# monitor.net
KiCad netlist of a schematic drawn in Altium Designer
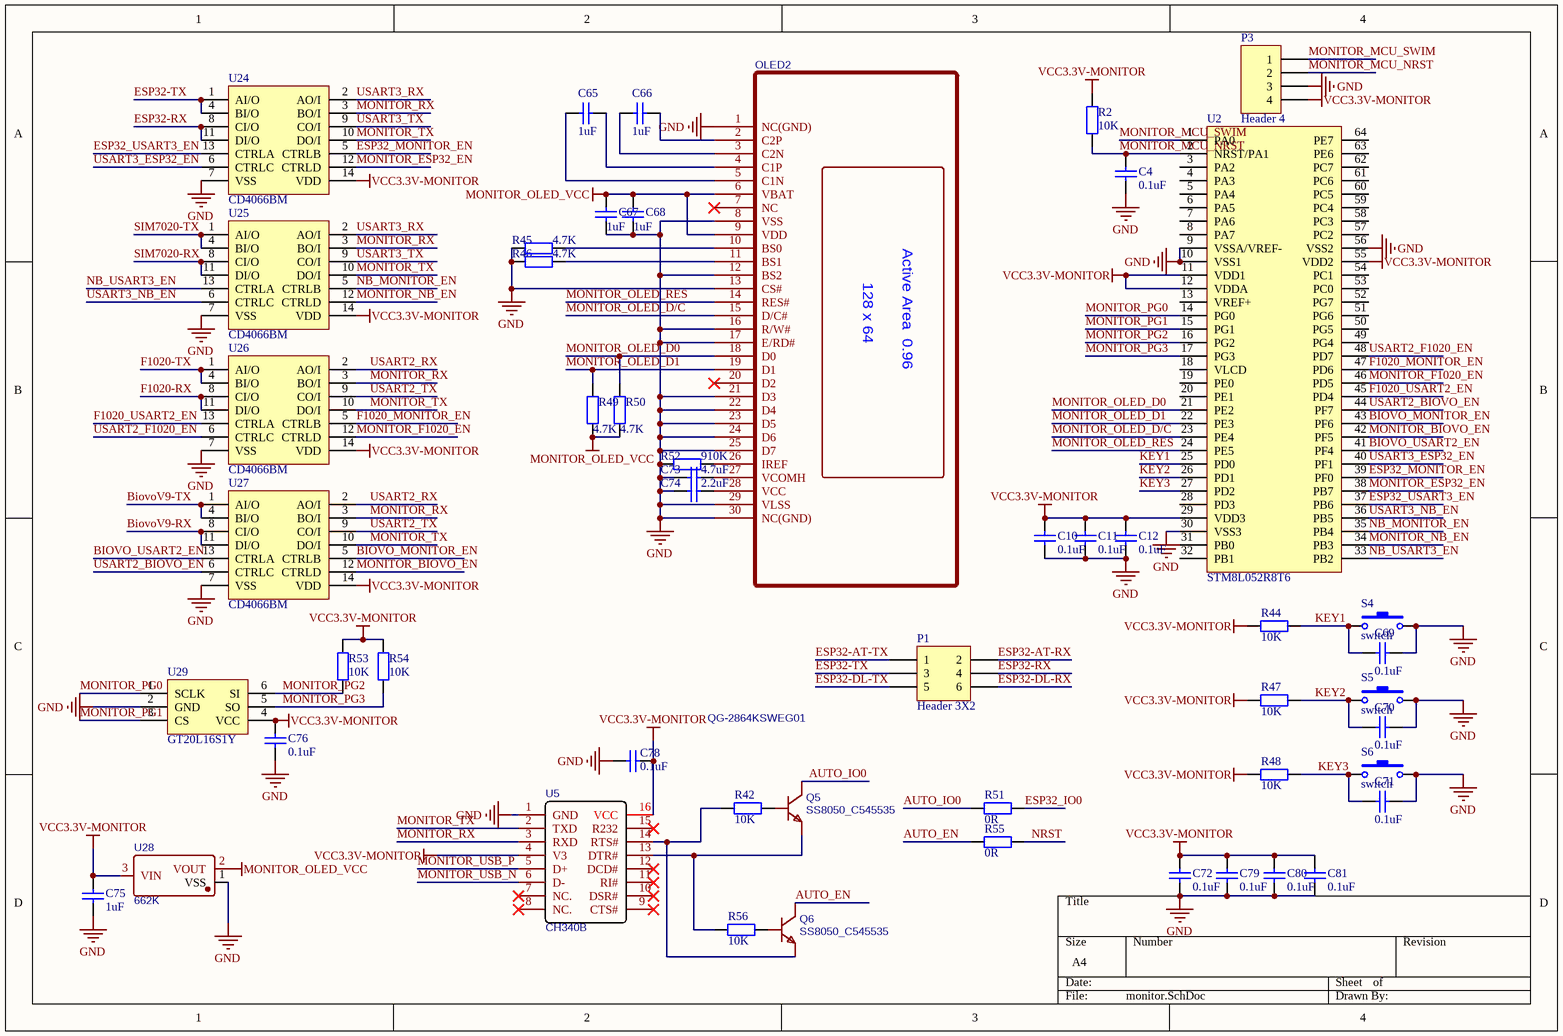
[diagram p0: monitor.SchDoc]

(export (version "E")
  (design (tool "Eeschema 10.0.6"))
  (components
    (comp (ref "C4")
      (value "0.1uF")
      (footprint "0603_C")
      (description "贴片电容，0603")
      (libsource (lib "stm8l052r8t6开发板") (part "Cap"))
    )
    (comp (ref "C10")
      (value "0.1uF")
      (footprint "0603_C")
      (description "贴片电容，0603")
      (libsource (lib "stm8l052r8t6开发板") (part "Cap"))
    )
    (comp (ref "C11")
      (value "0.1uF")
      (footprint "0603_C")
      (description "贴片电容，0603")
      (libsource (lib "stm8l052r8t6开发板") (part "Cap"))
    )
    (comp (ref "C12")
      (value "0.1uF")
      (footprint "0603_C")
      (description "贴片电容，0603")
      (libsource (lib "stm8l052r8t6开发板") (part "Cap"))
    )
    (comp (ref "C65")
      (value "1uF")
      (footprint "0603_C")
      (description "贴片电容，0603")
      (libsource (lib "stm8l052r8t6开发板") (part "Cap"))
    )
    (comp (ref "C66")
      (value "1uF")
      (footprint "0603_C")
      (description "贴片电容，0603")
      (libsource (lib "stm8l052r8t6开发板") (part "Cap"))
    )
    (comp (ref "C67")
      (value "1uF")
      (footprint "0603_C")
      (description "贴片电容，0603")
      (libsource (lib "stm8l052r8t6开发板") (part "Cap"))
    )
    (comp (ref "C68")
      (value "1uF")
      (footprint "0603_C")
      (description "贴片电容，0603")
      (libsource (lib "stm8l052r8t6开发板") (part "Cap"))
    )
    (comp (ref "C69")
      (value "0.1uF")
      (footprint "0603_C")
      (description "贴片电容，0603")
      (libsource (lib "extendBoard") (part "Cap"))
    )
    (comp (ref "C70")
      (value "0.1uF")
      (footprint "0603_C")
      (description "贴片电容，0603")
      (libsource (lib "extendBoard") (part "Cap"))
    )
    (comp (ref "C71")
      (value "0.1uF")
      (footprint "0603_C")
      (description "贴片电容，0603")
      (libsource (lib "extendBoard") (part "Cap"))
    )
    (comp (ref "C72")
      (value "0.1uF")
      (footprint "0603_C")
      (description "贴片电容，0603")
      (libsource (lib "extendBoard") (part "Cap"))
    )
    (comp (ref "C73")
      (value "4.7uF")
      (footprint "0603_C")
      (description "贴片电容，0603")
      (libsource (lib "stm8l052r8t6开发板") (part "Cap"))
    )
    (comp (ref "C74")
      (value "2.2uF")
      (footprint "0603_C")
      (description "贴片电容，0603")
      (libsource (lib "stm8l052r8t6开发板") (part "Cap"))
    )
    (comp (ref "C75")
      (value "1uF")
      (footprint "0603_C")
      (description "贴片电容，0603")
      (libsource (lib "stm8l052r8t6开发板") (part "Cap"))
    )
    (comp (ref "C76")
      (value "0.1uF")
      (footprint "0603_C")
      (description "贴片电容，0603")
      (libsource (lib "stm8l052r8t6开发板") (part "Cap"))
    )
    (comp (ref "C78")
      (value "0.1uF")
      (footprint "0603_C")
      (description "贴片电容，0603")
      (libsource (lib "extendBoard") (part "Cap"))
    )
    (comp (ref "C79")
      (value "0.1uF")
      (footprint "0603_C")
      (description "贴片电容，0603")
      (libsource (lib "extendBoard") (part "Cap"))
    )
    (comp (ref "C80")
      (value "0.1uF")
      (footprint "0603_C")
      (description "贴片电容，0603")
      (libsource (lib "extendBoard") (part "Cap"))
    )
    (comp (ref "C81")
      (value "0.1uF")
      (footprint "0603_C")
      (description "贴片电容，0603")
      (libsource (lib "extendBoard") (part "Cap"))
    )
    (comp (ref "OLED2")
      (value "QG-2864KSWEG01")
      (footprint "OLED-SMD_QG-2864KSWEG01-flod")
      (description "128x64 单色白色，QG-2864KSWEG01")
      (fields (field (name "BOM_SUPPLIER PART") "C85007"))
      (libsource (lib "stm8l052r8t6开发板") (part "QG-2864KSWEG01"))
    )
    (comp (ref "P1")
      (value "Header 3X2")
      (footprint "HDR2X3")
      (description "Header, 3-Pin, Dual row")
      (fields (field (name "PUBLISHER") "Altium Limited"))
      (libsource (lib "Miscellaneous Connectors") (part "Header 3X2"))
    )
    (comp (ref "P3")
      (value "Header 4")
      (footprint "HDR1X4")
      (description "不焊")
      (fields (field (name "PUBLISHER") "Altium Limited"))
      (libsource (lib "Miscellaneous Connectors") (part "Header 4"))
    )
    (comp (ref "Q5")
      (value "SS8050_C545535")
      (footprint "SOT-23-3_L2.9-W1.3-P1.90-LS2.4-BR")
      (description "S8050,SOT-23")
      (libsource (lib "stm8l052r8t6开发板") (part "SS8050_C545535"))
    )
    (comp (ref "Q6")
      (value "SS8050_C545535")
      (footprint "SOT-23-3_L2.9-W1.3-P1.90-LS2.4-BR")
      (description "S8050,SOT-23")
      (libsource (lib "stm8l052r8t6开发板") (part "SS8050_C545535"))
    )
    (comp (ref "R2")
      (value "10K")
      (footprint "0603_R")
      (description "贴片电阻，0603")
      (libsource (lib "stm8l052r8t6开发板") (part "Res2"))
    )
    (comp (ref "R42")
      (value "10K")
      (footprint "0603_R")
      (description "贴片电阻，0603")
      (libsource (lib "extendBoard") (part "Res2"))
    )
    (comp (ref "R44")
      (value "10K")
      (footprint "0603_R")
      (description "贴片电阻，0603")
      (libsource (lib "") (part "Res2_2"))
    )
    (comp (ref "R45")
      (value "4.7K")
      (footprint "0603_R")
      (description "贴片电阻，0603")
      (libsource (lib "") (part "Res2_1"))
    )
    (comp (ref "R46")
      (value "4.7K")
      (footprint "0603_R")
      (description "贴片电阻，0603")
      (libsource (lib "") (part "Res2_1"))
    )
    (comp (ref "R47")
      (value "10K")
      (footprint "0603_R")
      (description "贴片电阻，0603")
      (libsource (lib "") (part "Res2_2"))
    )
    (comp (ref "R48")
      (value "10K")
      (footprint "0603_R")
      (description "贴片电阻，0603")
      (libsource (lib "") (part "Res2_2"))
    )
    (comp (ref "R49")
      (value "4.7K")
      (footprint "0603_R")
      (description "贴片电阻，0603")
      (libsource (lib "stm8l052r8t6开发板") (part "Res2"))
    )
    (comp (ref "R50")
      (value "4.7K")
      (footprint "0603_R")
      (description "贴片电阻，0603")
      (libsource (lib "stm8l052r8t6开发板") (part "Res2"))
    )
    (comp (ref "R51")
      (value "0R")
      (footprint "0603_R")
      (description "贴片电阻，0603")
      (libsource (lib "extendBoard") (part "Res2"))
    )
    (comp (ref "R52")
      (value "910K")
      (footprint "0603_R")
      (description "贴片电阻，0603")
      (libsource (lib "") (part "Res2_2"))
    )
    (comp (ref "R53")
      (value "10K")
      (footprint "0603_R")
      (description "贴片电阻，0603")
      (libsource (lib "stm8l052r8t6开发板") (part "Res2"))
    )
    (comp (ref "R54")
      (value "10K")
      (footprint "0603_R")
      (description "贴片电阻，0603")
      (libsource (lib "stm8l052r8t6开发板") (part "Res2"))
    )
    (comp (ref "R55")
      (value "0R")
      (footprint "0603_R")
      (description "贴片电阻，0603")
      (libsource (lib "extendBoard") (part "Res2"))
    )
    (comp (ref "R56")
      (value "10K")
      (footprint "0603_R")
      (description "贴片电阻，0603")
      (libsource (lib "extendBoard") (part "Res2"))
    )
    (comp (ref "S4")
      (value "switch")
      (footprint "SW-SMD_4P-L6.2-W6.2-P4.50-LS9.0")
      (description "贴片按键，6*6*5")
      (libsource (lib "stm8l052r8t6开发板") (part "switch"))
    )
    (comp (ref "S5")
      (value "switch")
      (footprint "SW-SMD_4P-L6.2-W6.2-P4.50-LS9.0")
      (description "贴片按键，6*6*5")
      (libsource (lib "stm8l052r8t6开发板") (part "switch"))
    )
    (comp (ref "S6")
      (value "switch")
      (footprint "SW-SMD_4P-L6.2-W6.2-P4.50-LS9.0")
      (description "贴片按键，6*6*5")
      (libsource (lib "stm8l052r8t6开发板") (part "switch"))
    )
    (comp (ref "U2")
      (value "STM8L052R8T6")
      (footprint "LQFP-64_10X10X05P")
      (description "STM8L052R8T6,LQFP-64_10x10x05P")
      (libsource (lib "stm8l052r8t6开发板") (part "STM8L052R8T6"))
    )
    (comp (ref "U5")
      (value "CH340B")
      (footprint "SOP-16_L10.0-W3.9-P1.27-LS6.0-BL")
      (description "CH340B,SOP-16_150mil")
      (libsource (lib "stm8l052r8t6开发板") (part "CH340C"))
    )
    (comp (ref "U24")
      (value "CD4066BM")
      (footprint "SOIC-14_L8.7-W3.9-P1.27-LS6.0-BL")
      (description "双向 FET 开关,CD4066BM,SOIC-14")
      (libsource (lib "stm8l052r8t6开发板") (part "CD4066B"))
    )
    (comp (ref "U25")
      (value "CD4066BM")
      (footprint "SOIC-14_L8.7-W3.9-P1.27-LS6.0-BL")
      (description "双向 FET 开关,CD4066BM,SOIC-14")
      (libsource (lib "stm8l052r8t6开发板") (part "CD4066B"))
    )
    (comp (ref "U26")
      (value "CD4066BM")
      (footprint "SOIC-14_L8.7-W3.9-P1.27-LS6.0-BL")
      (description "双向 FET 开关,CD4066BM,SOIC-14")
      (libsource (lib "stm8l052r8t6开发板") (part "CD4066B"))
    )
    (comp (ref "U27")
      (value "CD4066BM")
      (footprint "SOIC-14_L8.7-W3.9-P1.27-LS6.0-BL")
      (description "双向 FET 开关,CD4066BM,SOIC-14")
      (libsource (lib "stm8l052r8t6开发板") (part "CD4066B"))
    )
    (comp (ref "U28")
      (value "662K")
      (footprint "SOT-23(SOT-23-3)")
      (description "线性稳压器662k,SOT23-3")
      (libsource (lib "stm8l052r8t6开发板") (part "662K"))
    )
    (comp (ref "U29")
      (value "GT20L16S1Y")
      (footprint "SOT-23-6")
      (description "字库芯片， SOT-23-6")
      (libsource (lib "stm8l052r8t6开发板") (part "GT20L16S1Y"))
    )
  )
  (nets
    (net (code "1") (name "/AUTO_EN") (class "Default")
      (node (ref "Q6") (pin "3") (pinfunction "C_3") (pintype "passive"))
      (node (ref "R55") (pin "2") (pinfunction "2_2") (pintype "passive"))
    )
    (net (code "2") (name "/AUTO_IO0") (class "Default")
      (node (ref "Q5") (pin "3") (pinfunction "C_3") (pintype "passive"))
      (node (ref "R51") (pin "2") (pinfunction "2_2") (pintype "passive"))
    )
    (net (code "3") (name "/BIOVO_MONITOR_EN") (class "Default")
      (node (ref "U2") (pin "43") (pinfunction "PF6_43") (pintype "passive"))
      (node (ref "U27") (pin "5") (pinfunction "CTRLB_5") (pintype "passive"))
    )
    (net (code "4") (name "/BIOVO_USART2_EN") (class "Default")
      (node (ref "U2") (pin "41") (pinfunction "PF4_41") (pintype "passive"))
      (node (ref "U27") (pin "13") (pinfunction "CTRLA_13") (pintype "passive"))
    )
    (net (code "5") (name "/BiovoV9-RX") (class "Default")
      (node (ref "U27") (pin "11") (pinfunction "DI/O_11") (pintype "passive"))
      (node (ref "U27") (pin "8") (pinfunction "CI/O_8") (pintype "passive"))
    )
    (net (code "6") (name "/BiovoV9-TX") (class "Default")
      (node (ref "U27") (pin "1") (pinfunction "AI/O_1") (pintype "passive"))
      (node (ref "U27") (pin "4") (pinfunction "BI/O_4") (pintype "passive"))
    )
    (net (code "7") (name "/ESP32-AT-RX") (class "Default")
      (node (ref "P1") (pin "2") (pinfunction "2_2") (pintype "passive"))
    )
    (net (code "8") (name "/ESP32-AT-TX") (class "Default")
      (node (ref "P1") (pin "1") (pinfunction "1_1") (pintype "passive"))
    )
    (net (code "9") (name "/ESP32-DL-RX") (class "Default")
      (node (ref "P1") (pin "6") (pinfunction "6_6") (pintype "passive"))
    )
    (net (code "10") (name "/ESP32-DL-TX") (class "Default")
      (node (ref "P1") (pin "5") (pinfunction "5_5") (pintype "passive"))
    )
    (net (code "11") (name "/ESP32-RX") (class "Default")
      (node (ref "P1") (pin "4") (pinfunction "4_4") (pintype "passive"))
      (node (ref "U24") (pin "11") (pinfunction "DI/O_11") (pintype "passive"))
      (node (ref "U24") (pin "8") (pinfunction "CI/O_8") (pintype "passive"))
    )
    (net (code "12") (name "/ESP32-TX") (class "Default")
      (node (ref "P1") (pin "3") (pinfunction "3_3") (pintype "passive"))
      (node (ref "U24") (pin "1") (pinfunction "AI/O_1") (pintype "passive"))
      (node (ref "U24") (pin "4") (pinfunction "BI/O_4") (pintype "passive"))
    )
    (net (code "13") (name "/ESP32_IO0") (class "Default")
      (node (ref "R51") (pin "1") (pinfunction "1_1") (pintype "passive"))
    )
    (net (code "14") (name "/ESP32_MONITOR_EN") (class "Default")
      (node (ref "U2") (pin "39") (pinfunction "PF0_39") (pintype "passive"))
      (node (ref "U24") (pin "5") (pinfunction "CTRLB_5") (pintype "passive"))
    )
    (net (code "15") (name "/ESP32_USART3_EN") (class "Default")
      (node (ref "U2") (pin "37") (pinfunction "PB6_37") (pintype "passive"))
      (node (ref "U24") (pin "13") (pinfunction "CTRLA_13") (pintype "passive"))
    )
    (net (code "16") (name "/F1020-RX") (class "Default")
      (node (ref "U26") (pin "11") (pinfunction "DI/O_11") (pintype "passive"))
      (node (ref "U26") (pin "8") (pinfunction "CI/O_8") (pintype "passive"))
    )
    (net (code "17") (name "/F1020-TX") (class "Default")
      (node (ref "U26") (pin "1") (pinfunction "AI/O_1") (pintype "passive"))
      (node (ref "U26") (pin "4") (pinfunction "BI/O_4") (pintype "passive"))
    )
    (net (code "18") (name "/F1020_MONITOR_EN") (class "Default")
      (node (ref "U2") (pin "47") (pinfunction "PD6_47") (pintype "passive"))
      (node (ref "U26") (pin "5") (pinfunction "CTRLB_5") (pintype "passive"))
    )
    (net (code "19") (name "/F1020_USART2_EN") (class "Default")
      (node (ref "U2") (pin "45") (pinfunction "PD4_45") (pintype "passive"))
      (node (ref "U26") (pin "13") (pinfunction "CTRLA_13") (pintype "passive"))
    )
    (net (code "20") (name "/KEY1") (class "Default")
      (node (ref "C69") (pin "2") (pinfunction "2_2") (pintype "passive"))
      (node (ref "R44") (pin "1") (pinfunction "1_1") (pintype "passive"))
      (node (ref "S4") (pin "1") (pinfunction "1_1") (pintype "passive"))
      (node (ref "U2") (pin "25") (pinfunction "PD0_25") (pintype "passive"))
    )
    (net (code "21") (name "/KEY2") (class "Default")
      (node (ref "C70") (pin "2") (pinfunction "2_2") (pintype "passive"))
      (node (ref "R47") (pin "1") (pinfunction "1_1") (pintype "passive"))
      (node (ref "S5") (pin "1") (pinfunction "1_1") (pintype "passive"))
      (node (ref "U2") (pin "26") (pinfunction "PD1_26") (pintype "passive"))
    )
    (net (code "22") (name "/KEY3") (class "Default")
      (node (ref "C71") (pin "2") (pinfunction "2_2") (pintype "passive"))
      (node (ref "R48") (pin "1") (pinfunction "1_1") (pintype "passive"))
      (node (ref "S6") (pin "1") (pinfunction "1_1") (pintype "passive"))
      (node (ref "U2") (pin "27") (pinfunction "PD2_27") (pintype "passive"))
    )
    (net (code "23") (name "/MONITOR_BIOVO_EN") (class "Default")
      (node (ref "U2") (pin "42") (pinfunction "PF5_42") (pintype "passive"))
      (node (ref "U27") (pin "12") (pinfunction "CTRLD_12") (pintype "passive"))
    )
    (net (code "24") (name "/MONITOR_ESP32_EN") (class "Default")
      (node (ref "U2") (pin "38") (pinfunction "PB7_38") (pintype "passive"))
      (node (ref "U24") (pin "12") (pinfunction "CTRLD_12") (pintype "passive"))
    )
    (net (code "25") (name "/MONITOR_F1020_EN") (class "Default")
      (node (ref "U2") (pin "46") (pinfunction "PD5_46") (pintype "passive"))
      (node (ref "U26") (pin "12") (pinfunction "CTRLD_12") (pintype "passive"))
    )
    (net (code "26") (name "/MONITOR_MCU_NRST") (class "Default")
      (node (ref "C4") (pin "2") (pinfunction "2_2") (pintype "passive"))
      (node (ref "P3") (pin "2") (pinfunction "2_2") (pintype "passive"))
      (node (ref "R2") (pin "1") (pinfunction "1_1") (pintype "passive"))
      (node (ref "U2") (pin "2") (pinfunction "NRST/PA1_2") (pintype "passive"))
    )
    (net (code "27") (name "/MONITOR_MCU_SWIM") (class "Default")
      (node (ref "P3") (pin "1") (pinfunction "1_1") (pintype "passive"))
      (node (ref "U2") (pin "1") (pinfunction "PA0_1") (pintype "passive"))
    )
    (net (code "28") (name "/MONITOR_NB_EN") (class "Default")
      (node (ref "U2") (pin "34") (pinfunction "PB3_34") (pintype "passive"))
      (node (ref "U25") (pin "12") (pinfunction "CTRLD_12") (pintype "passive"))
    )
    (net (code "29") (name "/MONITOR_OLED_D0") (class "Default")
      (node (ref "OLED2") (pin "18") (pinfunction "D0_18") (pintype "passive"))
      (node (ref "R50") (pin "2") (pinfunction "2_2") (pintype "passive"))
      (node (ref "U2") (pin "21") (pinfunction "PE2_21") (pintype "passive"))
    )
    (net (code "30") (name "/MONITOR_OLED_D1") (class "Default")
      (node (ref "OLED2") (pin "19") (pinfunction "D1_19") (pintype "passive"))
      (node (ref "R49") (pin "2") (pinfunction "2_2") (pintype "passive"))
      (node (ref "U2") (pin "22") (pinfunction "PE3_22") (pintype "passive"))
    )
    (net (code "31") (name "/MONITOR_OLED_D{slash}C") (class "Default")
      (node (ref "OLED2") (pin "15") (pinfunction "D/C#_15") (pintype "passive"))
      (node (ref "U2") (pin "23") (pinfunction "PE4_23") (pintype "passive"))
    )
    (net (code "32") (name "/MONITOR_OLED_RES") (class "Default")
      (node (ref "OLED2") (pin "14") (pinfunction "RES#_14") (pintype "passive"))
      (node (ref "U2") (pin "24") (pinfunction "PE5_24") (pintype "passive"))
    )
    (net (code "33") (name "/MONITOR_PG0") (class "Default")
      (node (ref "U2") (pin "14") (pinfunction "PG0_14") (pintype "passive"))
      (node (ref "U29") (pin "1") (pinfunction "SCLK_1") (pintype "passive"))
    )
    (net (code "34") (name "/MONITOR_PG1") (class "Default")
      (node (ref "U2") (pin "15") (pinfunction "PG1_15") (pintype "passive"))
      (node (ref "U29") (pin "3") (pinfunction "CS_3") (pintype "passive"))
    )
    (net (code "35") (name "/MONITOR_PG2") (class "Default")
      (node (ref "R53") (pin "1") (pinfunction "1_1") (pintype "passive"))
      (node (ref "U2") (pin "16") (pinfunction "PG2_16") (pintype "passive"))
      (node (ref "U29") (pin "6") (pinfunction "SI_6") (pintype "passive"))
    )
    (net (code "36") (name "/MONITOR_PG3") (class "Default")
      (node (ref "R54") (pin "1") (pinfunction "1_1") (pintype "passive"))
      (node (ref "U2") (pin "17") (pinfunction "PG3_17") (pintype "passive"))
      (node (ref "U29") (pin "5") (pinfunction "SO_5") (pintype "passive"))
    )
    (net (code "37") (name "/MONITOR_RX") (class "Default")
      (node (ref "U24") (pin "3") (pinfunction "BO/I_3") (pintype "passive"))
      (node (ref "U25") (pin "3") (pinfunction "BO/I_3") (pintype "passive"))
      (node (ref "U26") (pin "3") (pinfunction "BO/I_3") (pintype "passive"))
      (node (ref "U27") (pin "3") (pinfunction "BO/I_3") (pintype "passive"))
      (node (ref "U5") (pin "3") (pinfunction "RXD_3") (pintype "passive"))
    )
    (net (code "38") (name "/MONITOR_TX") (class "Default")
      (node (ref "U24") (pin "10") (pinfunction "DO/I_10") (pintype "passive"))
      (node (ref "U25") (pin "10") (pinfunction "DO/I_10") (pintype "passive"))
      (node (ref "U26") (pin "10") (pinfunction "DO/I_10") (pintype "passive"))
      (node (ref "U27") (pin "10") (pinfunction "DO/I_10") (pintype "passive"))
      (node (ref "U5") (pin "2") (pinfunction "TXD_2") (pintype "passive"))
    )
    (net (code "39") (name "/MONITOR_USB_N") (class "Default")
      (node (ref "U5") (pin "6") (pinfunction "D-_6") (pintype "passive"))
    )
    (net (code "40") (name "/MONITOR_USB_P") (class "Default")
      (node (ref "U5") (pin "5") (pinfunction "D+_5") (pintype "passive"))
    )
    (net (code "41") (name "/NB_MONITOR_EN") (class "Default")
      (node (ref "U2") (pin "35") (pinfunction "PB4_35") (pintype "passive"))
      (node (ref "U25") (pin "5") (pinfunction "CTRLB_5") (pintype "passive"))
    )
    (net (code "42") (name "/NB_USART3_EN") (class "Default")
      (node (ref "U2") (pin "33") (pinfunction "PB2_33") (pintype "passive"))
      (node (ref "U25") (pin "13") (pinfunction "CTRLA_13") (pintype "passive"))
    )
    (net (code "43") (name "/NRST") (class "Default")
      (node (ref "R55") (pin "1") (pinfunction "1_1") (pintype "passive"))
    )
    (net (code "44") (name "/SIM7020-RX") (class "Default")
      (node (ref "U25") (pin "11") (pinfunction "DI/O_11") (pintype "passive"))
      (node (ref "U25") (pin "8") (pinfunction "CI/O_8") (pintype "passive"))
    )
    (net (code "45") (name "/SIM7020-TX") (class "Default")
      (node (ref "U25") (pin "1") (pinfunction "AI/O_1") (pintype "passive"))
      (node (ref "U25") (pin "4") (pinfunction "BI/O_4") (pintype "passive"))
    )
    (net (code "46") (name "/USART2_BIOVO_EN") (class "Default")
      (node (ref "U2") (pin "44") (pinfunction "PF7_44") (pintype "passive"))
      (node (ref "U27") (pin "6") (pinfunction "CTRLC_6") (pintype "passive"))
    )
    (net (code "47") (name "/USART2_F1020_EN") (class "Default")
      (node (ref "U2") (pin "48") (pinfunction "PD7_48") (pintype "passive"))
      (node (ref "U26") (pin "6") (pinfunction "CTRLC_6") (pintype "passive"))
    )
    (net (code "48") (name "/USART2_RX") (class "Default")
      (node (ref "U26") (pin "2") (pinfunction "AO/I_2") (pintype "passive"))
      (node (ref "U27") (pin "2") (pinfunction "AO/I_2") (pintype "passive"))
    )
    (net (code "49") (name "/USART2_TX") (class "Default")
      (node (ref "U26") (pin "9") (pinfunction "CO/I_9") (pintype "passive"))
      (node (ref "U27") (pin "9") (pinfunction "CO/I_9") (pintype "passive"))
    )
    (net (code "50") (name "/USART3_ESP32_EN") (class "Default")
      (node (ref "U2") (pin "40") (pinfunction "PF1_40") (pintype "passive"))
      (node (ref "U24") (pin "6") (pinfunction "CTRLC_6") (pintype "passive"))
    )
    (net (code "51") (name "/USART3_NB_EN") (class "Default")
      (node (ref "U2") (pin "36") (pinfunction "PB5_36") (pintype "passive"))
      (node (ref "U25") (pin "6") (pinfunction "CTRLC_6") (pintype "passive"))
    )
    (net (code "52") (name "/USART3_RX") (class "Default")
      (node (ref "U24") (pin "2") (pinfunction "AO/I_2") (pintype "passive"))
      (node (ref "U25") (pin "2") (pinfunction "AO/I_2") (pintype "passive"))
    )
    (net (code "53") (name "/USART3_TX") (class "Default")
      (node (ref "U24") (pin "9") (pinfunction "CO/I_9") (pintype "passive"))
      (node (ref "U25") (pin "9") (pinfunction "CO/I_9") (pintype "passive"))
    )
    (net (code "54") (name "GND") (class "Default")
      (node (ref "C10") (pin "1") (pinfunction "1_1") (pintype "passive"))
      (node (ref "C11") (pin "1") (pinfunction "1_1") (pintype "passive"))
      (node (ref "C12") (pin "1") (pinfunction "1_1") (pintype "passive"))
      (node (ref "C4") (pin "1") (pinfunction "1_1") (pintype "passive"))
      (node (ref "C67") (pin "2") (pinfunction "2_2") (pintype "passive"))
      (node (ref "C68") (pin "2") (pinfunction "2_2") (pintype "passive"))
      (node (ref "C69") (pin "1") (pinfunction "1_1") (pintype "passive"))
      (node (ref "C70") (pin "1") (pinfunction "1_1") (pintype "passive"))
      (node (ref "C71") (pin "1") (pinfunction "1_1") (pintype "passive"))
      (node (ref "C72") (pin "1") (pinfunction "1_1") (pintype "passive"))
      (node (ref "C73") (pin "1") (pinfunction "1_1") (pintype "passive"))
      (node (ref "C74") (pin "1") (pinfunction "1_1") (pintype "passive"))
      (node (ref "C75") (pin "2") (pinfunction "2_2") (pintype "passive"))
      (node (ref "C76") (pin "1") (pinfunction "1_1") (pintype "passive"))
      (node (ref "C78") (pin "1") (pinfunction "1_1") (pintype "passive"))
      (node (ref "C79") (pin "1") (pinfunction "1_1") (pintype "passive"))
      (node (ref "C80") (pin "1") (pinfunction "1_1") (pintype "passive"))
      (node (ref "C81") (pin "1") (pinfunction "1_1") (pintype "passive"))
      (node (ref "OLED2") (pin "1") (pinfunction "NC(GND)_1") (pintype "passive"))
      (node (ref "OLED2") (pin "12") (pinfunction "BS2_12") (pintype "passive"))
      (node (ref "OLED2") (pin "13") (pinfunction "CS#_13") (pintype "passive"))
      (node (ref "OLED2") (pin "16") (pinfunction "R/W#_16") (pintype "passive"))
      (node (ref "OLED2") (pin "17") (pinfunction "E/RD#_17") (pintype "passive"))
      (node (ref "OLED2") (pin "21") (pinfunction "D3_21") (pintype "passive"))
      (node (ref "OLED2") (pin "22") (pinfunction "D4_22") (pintype "passive"))
      (node (ref "OLED2") (pin "23") (pinfunction "D5_23") (pintype "passive"))
      (node (ref "OLED2") (pin "24") (pinfunction "D6_24") (pintype "passive"))
      (node (ref "OLED2") (pin "25") (pinfunction "D7_25") (pintype "passive"))
      (node (ref "OLED2") (pin "29") (pinfunction "VLSS_29") (pintype "passive"))
      (node (ref "OLED2") (pin "30") (pinfunction "NC(GND)_30") (pintype "passive"))
      (node (ref "OLED2") (pin "8") (pinfunction "VSS_8") (pintype "passive"))
      (node (ref "P3") (pin "3") (pinfunction "3_3") (pintype "passive"))
      (node (ref "R45") (pin "1") (pinfunction "1_1") (pintype "passive"))
      (node (ref "R46") (pin "1") (pinfunction "1_1") (pintype "passive"))
      (node (ref "R52") (pin "2") (pinfunction "2_2") (pintype "passive"))
      (node (ref "S4") (pin "2") (pinfunction "2_2") (pintype "passive"))
      (node (ref "S5") (pin "2") (pinfunction "2_2") (pintype "passive"))
      (node (ref "S6") (pin "2") (pinfunction "2_2") (pintype "passive"))
      (node (ref "U2") (pin "10") (pinfunction "VSS1_10") (pintype "passive"))
      (node (ref "U2") (pin "30") (pinfunction "VSS3_30") (pintype "passive"))
      (node (ref "U2") (pin "56") (pinfunction "VSS2_56") (pintype "passive"))
      (node (ref "U2") (pin "9") (pinfunction "VSSA/VREF-_9") (pintype "passive"))
      (node (ref "U24") (pin "7") (pinfunction "VSS_7") (pintype "passive"))
      (node (ref "U25") (pin "7") (pinfunction "VSS_7") (pintype "passive"))
      (node (ref "U26") (pin "7") (pinfunction "VSS_7") (pintype "passive"))
      (node (ref "U27") (pin "7") (pinfunction "VSS_7") (pintype "passive"))
      (node (ref "U28") (pin "1") (pinfunction "VSS_1") (pintype "passive"))
      (node (ref "U29") (pin "2") (pinfunction "GND_2") (pintype "passive"))
      (node (ref "U5") (pin "1") (pinfunction "GND_1") (pintype "passive"))
    )
    (net (code "55") (name "MONITOR_OLED_VCC") (class "Default")
      (node (ref "C67") (pin "1") (pinfunction "1_1") (pintype "passive"))
      (node (ref "C68") (pin "1") (pinfunction "1_1") (pintype "passive"))
      (node (ref "OLED2") (pin "6") (pinfunction "VBAT_6") (pintype "passive"))
      (node (ref "OLED2") (pin "9") (pinfunction "VDD_9") (pintype "passive"))
      (node (ref "R49") (pin "1") (pinfunction "1_1") (pintype "passive"))
      (node (ref "R50") (pin "1") (pinfunction "1_1") (pintype "passive"))
      (node (ref "U28") (pin "2") (pinfunction "VOUT_2") (pintype "passive"))
    )
    (net (code "56") (name "Net-(OLED2-BS0)") (class "Default")
      (node (ref "OLED2") (pin "10") (pinfunction "BS0_10") (pintype "passive"))
      (node (ref "R45") (pin "2") (pinfunction "2_2") (pintype "passive"))
    )
    (net (code "57") (name "Net-(OLED2-BS1)") (class "Default")
      (node (ref "OLED2") (pin "11") (pinfunction "BS1_11") (pintype "passive"))
      (node (ref "R46") (pin "2") (pinfunction "2_2") (pintype "passive"))
    )
    (net (code "58") (name "Net-(OLED2-C1N)") (class "Default")
      (node (ref "C65") (pin "2") (pinfunction "2_2") (pintype "passive"))
      (node (ref "OLED2") (pin "5") (pinfunction "C1N_5") (pintype "passive"))
    )
    (net (code "59") (name "Net-(OLED2-C1P)") (class "Default")
      (node (ref "C65") (pin "1") (pinfunction "1_1") (pintype "passive"))
      (node (ref "OLED2") (pin "4") (pinfunction "C1P_4") (pintype "passive"))
    )
    (net (code "60") (name "Net-(OLED2-C2N)") (class "Default")
      (node (ref "C66") (pin "2") (pinfunction "2_2") (pintype "passive"))
      (node (ref "OLED2") (pin "3") (pinfunction "C2N_3") (pintype "passive"))
    )
    (net (code "61") (name "Net-(OLED2-C2P)") (class "Default")
      (node (ref "C66") (pin "1") (pinfunction "1_1") (pintype "passive"))
      (node (ref "OLED2") (pin "2") (pinfunction "C2P_2") (pintype "passive"))
    )
    (net (code "62") (name "Net-(OLED2-IREF)") (class "Default")
      (node (ref "OLED2") (pin "26") (pinfunction "IREF_26") (pintype "passive"))
      (node (ref "R52") (pin "1") (pinfunction "1_1") (pintype "passive"))
    )
    (net (code "63") (name "Net-(OLED2-VCC)") (class "Default")
      (node (ref "C74") (pin "2") (pinfunction "2_2") (pintype "passive"))
      (node (ref "OLED2") (pin "28") (pinfunction "VCC_28") (pintype "passive"))
    )
    (net (code "64") (name "Net-(OLED2-VCOMH)") (class "Default")
      (node (ref "C73") (pin "2") (pinfunction "2_2") (pintype "passive"))
      (node (ref "OLED2") (pin "27") (pinfunction "VCOMH_27") (pintype "passive"))
    )
    (net (code "65") (name "Net-(Q5-B)") (class "Default")
      (node (ref "Q5") (pin "1") (pinfunction "B_1") (pintype "passive"))
      (node (ref "R42") (pin "1") (pinfunction "1_1") (pintype "passive"))
    )
    (net (code "66") (name "Net-(Q5-E)") (class "Default")
      (node (ref "Q5") (pin "2") (pinfunction "E_2") (pintype "passive"))
      (node (ref "R56") (pin "2") (pinfunction "2_2") (pintype "passive"))
      (node (ref "U5") (pin "13") (pinfunction "DTR#_13") (pintype "passive"))
    )
    (net (code "67") (name "Net-(Q6-B)") (class "Default")
      (node (ref "Q6") (pin "1") (pinfunction "B_1") (pintype "passive"))
      (node (ref "R56") (pin "1") (pinfunction "1_1") (pintype "passive"))
    )
    (net (code "68") (name "Net-(Q6-E)") (class "Default")
      (node (ref "Q6") (pin "2") (pinfunction "E_2") (pintype "passive"))
      (node (ref "R42") (pin "2") (pinfunction "2_2") (pintype "passive"))
      (node (ref "U5") (pin "14") (pinfunction "RTS#_14") (pintype "passive"))
    )
    (net (code "69") (name "VCC3.3V-MONITOR") (class "Default")
      (node (ref "C10") (pin "2") (pinfunction "2_2") (pintype "passive"))
      (node (ref "C11") (pin "2") (pinfunction "2_2") (pintype "passive"))
      (node (ref "C12") (pin "2") (pinfunction "2_2") (pintype "passive"))
      (node (ref "C72") (pin "2") (pinfunction "2_2") (pintype "passive"))
      (node (ref "C75") (pin "1") (pinfunction "1_1") (pintype "passive"))
      (node (ref "C76") (pin "2") (pinfunction "2_2") (pintype "passive"))
      (node (ref "C78") (pin "2") (pinfunction "2_2") (pintype "passive"))
      (node (ref "C79") (pin "2") (pinfunction "2_2") (pintype "passive"))
      (node (ref "C80") (pin "2") (pinfunction "2_2") (pintype "passive"))
      (node (ref "C81") (pin "2") (pinfunction "2_2") (pintype "passive"))
      (node (ref "P3") (pin "4") (pinfunction "4_4") (pintype "passive"))
      (node (ref "R2") (pin "2") (pinfunction "2_2") (pintype "passive"))
      (node (ref "R44") (pin "2") (pinfunction "2_2") (pintype "passive"))
      (node (ref "R47") (pin "2") (pinfunction "2_2") (pintype "passive"))
      (node (ref "R48") (pin "2") (pinfunction "2_2") (pintype "passive"))
      (node (ref "R53") (pin "2") (pinfunction "2_2") (pintype "passive"))
      (node (ref "R54") (pin "2") (pinfunction "2_2") (pintype "passive"))
      (node (ref "U2") (pin "11") (pinfunction "VDD1_11") (pintype "passive"))
      (node (ref "U2") (pin "12") (pinfunction "VDDA_12") (pintype "passive"))
      (node (ref "U2") (pin "29") (pinfunction "VDD3_29") (pintype "passive"))
      (node (ref "U2") (pin "55") (pinfunction "VDD2_55") (pintype "passive"))
      (node (ref "U24") (pin "14") (pinfunction "VDD_14") (pintype "passive"))
      (node (ref "U25") (pin "14") (pinfunction "VDD_14") (pintype "passive"))
      (node (ref "U26") (pin "14") (pinfunction "VDD_14") (pintype "passive"))
      (node (ref "U27") (pin "14") (pinfunction "VDD_14") (pintype "passive"))
      (node (ref "U28") (pin "3") (pinfunction "VIN_3") (pintype "passive"))
      (node (ref "U29") (pin "4") (pinfunction "VCC_4") (pintype "passive"))
      (node (ref "U5") (pin "16") (pinfunction "VCC_16") (pintype "passive"))
      (node (ref "U5") (pin "4") (pinfunction "V3_4") (pintype "passive"))
    )
    (net (code "70") (name "unconnected-(OLED2-D2-Pad20)") (class "Default")
      (node (ref "OLED2") (pin "20") (pinfunction "D2_20") (pintype "passive+no_connect"))
    )
    (net (code "71") (name "unconnected-(OLED2-NC-Pad7)") (class "Default")
      (node (ref "OLED2") (pin "7") (pinfunction "NC_7") (pintype "passive+no_connect"))
    )
    (net (code "72") (name "unconnected-(U2-PA2-Pad3)") (class "Default")
      (node (ref "U2") (pin "3") (pinfunction "PA2_3") (pintype "passive"))
    )
    (net (code "73") (name "unconnected-(U2-PA3-Pad4)") (class "Default")
      (node (ref "U2") (pin "4") (pinfunction "PA3_4") (pintype "passive"))
    )
    (net (code "74") (name "unconnected-(U2-PA4-Pad5)") (class "Default")
      (node (ref "U2") (pin "5") (pinfunction "PA4_5") (pintype "passive"))
    )
    (net (code "75") (name "unconnected-(U2-PA5-Pad6)") (class "Default")
      (node (ref "U2") (pin "6") (pinfunction "PA5_6") (pintype "passive"))
    )
    (net (code "76") (name "unconnected-(U2-PA6-Pad7)") (class "Default")
      (node (ref "U2") (pin "7") (pinfunction "PA6_7") (pintype "passive"))
    )
    (net (code "77") (name "unconnected-(U2-PA7-Pad8)") (class "Default")
      (node (ref "U2") (pin "8") (pinfunction "PA7_8") (pintype "passive"))
    )
    (net (code "78") (name "unconnected-(U2-PB0-Pad31)") (class "Default")
      (node (ref "U2") (pin "31") (pinfunction "PB0_31") (pintype "passive"))
    )
    (net (code "79") (name "unconnected-(U2-PB1-Pad32)") (class "Default")
      (node (ref "U2") (pin "32") (pinfunction "PB1_32") (pintype "passive"))
    )
    (net (code "80") (name "unconnected-(U2-PC0-Pad53)") (class "Default")
      (node (ref "U2") (pin "53") (pinfunction "PC0_53") (pintype "passive"))
    )
    (net (code "81") (name "unconnected-(U2-PC1-Pad54)") (class "Default")
      (node (ref "U2") (pin "54") (pinfunction "PC1_54") (pintype "passive"))
    )
    (net (code "82") (name "unconnected-(U2-PC2-Pad57)") (class "Default")
      (node (ref "U2") (pin "57") (pinfunction "PC2_57") (pintype "passive"))
    )
    (net (code "83") (name "unconnected-(U2-PC3-Pad58)") (class "Default")
      (node (ref "U2") (pin "58") (pinfunction "PC3_58") (pintype "passive"))
    )
    (net (code "84") (name "unconnected-(U2-PC4-Pad59)") (class "Default")
      (node (ref "U2") (pin "59") (pinfunction "PC4_59") (pintype "passive"))
    )
    (net (code "85") (name "unconnected-(U2-PC5-Pad60)") (class "Default")
      (node (ref "U2") (pin "60") (pinfunction "PC5_60") (pintype "passive"))
    )
    (net (code "86") (name "unconnected-(U2-PC6-Pad61)") (class "Default")
      (node (ref "U2") (pin "61") (pinfunction "PC6_61") (pintype "passive"))
    )
    (net (code "87") (name "unconnected-(U2-PC7-Pad62)") (class "Default")
      (node (ref "U2") (pin "62") (pinfunction "PC7_62") (pintype "passive"))
    )
    (net (code "88") (name "unconnected-(U2-PD3-Pad28)") (class "Default")
      (node (ref "U2") (pin "28") (pinfunction "PD3_28") (pintype "passive"))
    )
    (net (code "89") (name "unconnected-(U2-PE0-Pad19)") (class "Default")
      (node (ref "U2") (pin "19") (pinfunction "PE0_19") (pintype "passive"))
    )
    (net (code "90") (name "unconnected-(U2-PE1-Pad20)") (class "Default")
      (node (ref "U2") (pin "20") (pinfunction "PE1_20") (pintype "passive"))
    )
    (net (code "91") (name "unconnected-(U2-PE6-Pad63)") (class "Default")
      (node (ref "U2") (pin "63") (pinfunction "PE6_63") (pintype "passive"))
    )
    (net (code "92") (name "unconnected-(U2-PE7-Pad64)") (class "Default")
      (node (ref "U2") (pin "64") (pinfunction "PE7_64") (pintype "passive"))
    )
    (net (code "93") (name "unconnected-(U2-PG4-Pad49)") (class "Default")
      (node (ref "U2") (pin "49") (pinfunction "PG4_49") (pintype "passive"))
    )
    (net (code "94") (name "unconnected-(U2-PG5-Pad50)") (class "Default")
      (node (ref "U2") (pin "50") (pinfunction "PG5_50") (pintype "passive"))
    )
    (net (code "95") (name "unconnected-(U2-PG6-Pad51)") (class "Default")
      (node (ref "U2") (pin "51") (pinfunction "PG6_51") (pintype "passive"))
    )
    (net (code "96") (name "unconnected-(U2-PG7-Pad52)") (class "Default")
      (node (ref "U2") (pin "52") (pinfunction "PG7_52") (pintype "passive"))
    )
    (net (code "97") (name "unconnected-(U2-VLCD-Pad18)") (class "Default")
      (node (ref "U2") (pin "18") (pinfunction "VLCD_18") (pintype "passive"))
    )
    (net (code "98") (name "unconnected-(U2-VREF+-Pad13)") (class "Default")
      (node (ref "U2") (pin "13") (pinfunction "VREF+_13") (pintype "passive"))
    )
    (net (code "99") (name "unconnected-(U5-CTS#-Pad9)") (class "Default")
      (node (ref "U5") (pin "9") (pinfunction "CTS#_9") (pintype "passive+no_connect"))
    )
    (net (code "100") (name "unconnected-(U5-DCD#-Pad12)") (class "Default")
      (node (ref "U5") (pin "12") (pinfunction "DCD#_12") (pintype "passive+no_connect"))
    )
    (net (code "101") (name "unconnected-(U5-DSR#-Pad10)") (class "Default")
      (node (ref "U5") (pin "10") (pinfunction "DSR#_10") (pintype "passive+no_connect"))
    )
    (net (code "102") (name "unconnected-(U5-NC.-Pad7)") (class "Default")
      (node (ref "U5") (pin "7") (pinfunction "NC._7") (pintype "passive+no_connect"))
    )
    (net (code "103") (name "unconnected-(U5-NC.-Pad8)") (class "Default")
      (node (ref "U5") (pin "8") (pinfunction "NC._8") (pintype "passive+no_connect"))
    )
    (net (code "104") (name "unconnected-(U5-R232-Pad15)") (class "Default")
      (node (ref "U5") (pin "15") (pinfunction "R232_15") (pintype "passive+no_connect"))
    )
    (net (code "105") (name "unconnected-(U5-RI#-Pad11)") (class "Default")
      (node (ref "U5") (pin "11") (pinfunction "RI#_11") (pintype "passive+no_connect"))
    )
  )
)
